# power.net
KiCad netlist of a schematic drawn in Altium Designer
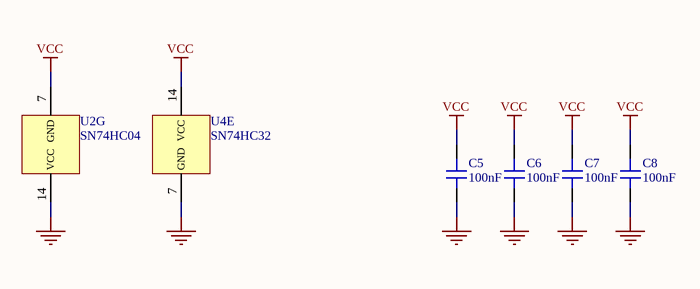
[diagram p0: power.SchDoc]

(export (version "E")
  (design (tool "Eeschema 10.0.6"))
  (components
    (comp (ref "C5")
      (value "100nF")
      (footprint "DiskCapacitor")
      (description "Capacitor")
      (libsource (lib "Basic") (part "Capacitor"))
    )
    (comp (ref "C6")
      (value "100nF")
      (footprint "DiskCapacitor")
      (description "Capacitor")
      (libsource (lib "Basic") (part "Capacitor"))
    )
    (comp (ref "C7")
      (value "100nF")
      (footprint "DiskCapacitor")
      (description "Capacitor")
      (libsource (lib "Basic") (part "Capacitor"))
    )
    (comp (ref "C8")
      (value "100nF")
      (footprint "DiskCapacitor")
      (description "Capacitor")
      (libsource (lib "Basic") (part "Capacitor"))
    )
    (comp (ref "U2")
      (value "SN74HC04")
      (footprint "TSSOP14")
      (description "Hex Inverters")
      (libsource (lib "Texas Instruments") (part "SN74HC04"))
    )
    (comp (ref "U4")
      (value "SN74HC32")
      (footprint "CDIP14")
      (description "Quadruple 2-Input Positive-OR Gates")
      (libsource (lib "Texas Instruments") (part "SN74HC32"))
    )
  )
  (nets
    (net (code "1") (name "GND") (class "Default")
      (node (ref "C5") (pin "1") (pinfunction "1_1") (pintype "passive"))
      (node (ref "C6") (pin "1") (pinfunction "1_1") (pintype "passive"))
      (node (ref "C7") (pin "1") (pinfunction "1_1") (pintype "passive"))
      (node (ref "C8") (pin "1") (pinfunction "1_1") (pintype "passive"))
      (node (ref "U2") (pin "14") (pinfunction "VCC_14") (pintype "power_in"))
      (node (ref "U4") (pin "7") (pinfunction "GND_7") (pintype "power_in"))
    )
    (net (code "2") (name "VCC") (class "Default")
      (node (ref "C5") (pin "2") (pinfunction "2_2") (pintype "passive"))
      (node (ref "C6") (pin "2") (pinfunction "2_2") (pintype "passive"))
      (node (ref "C7") (pin "2") (pinfunction "2_2") (pintype "passive"))
      (node (ref "C8") (pin "2") (pinfunction "2_2") (pintype "passive"))
      (node (ref "U2") (pin "7") (pinfunction "GND_7") (pintype "power_in"))
      (node (ref "U4") (pin "14") (pinfunction "VCC_14") (pintype "power_in"))
    )
  )
)
